# Forest-Joystick-Mouse-Hub.net
KiCad netlist of a schematic drawn in EAGLE
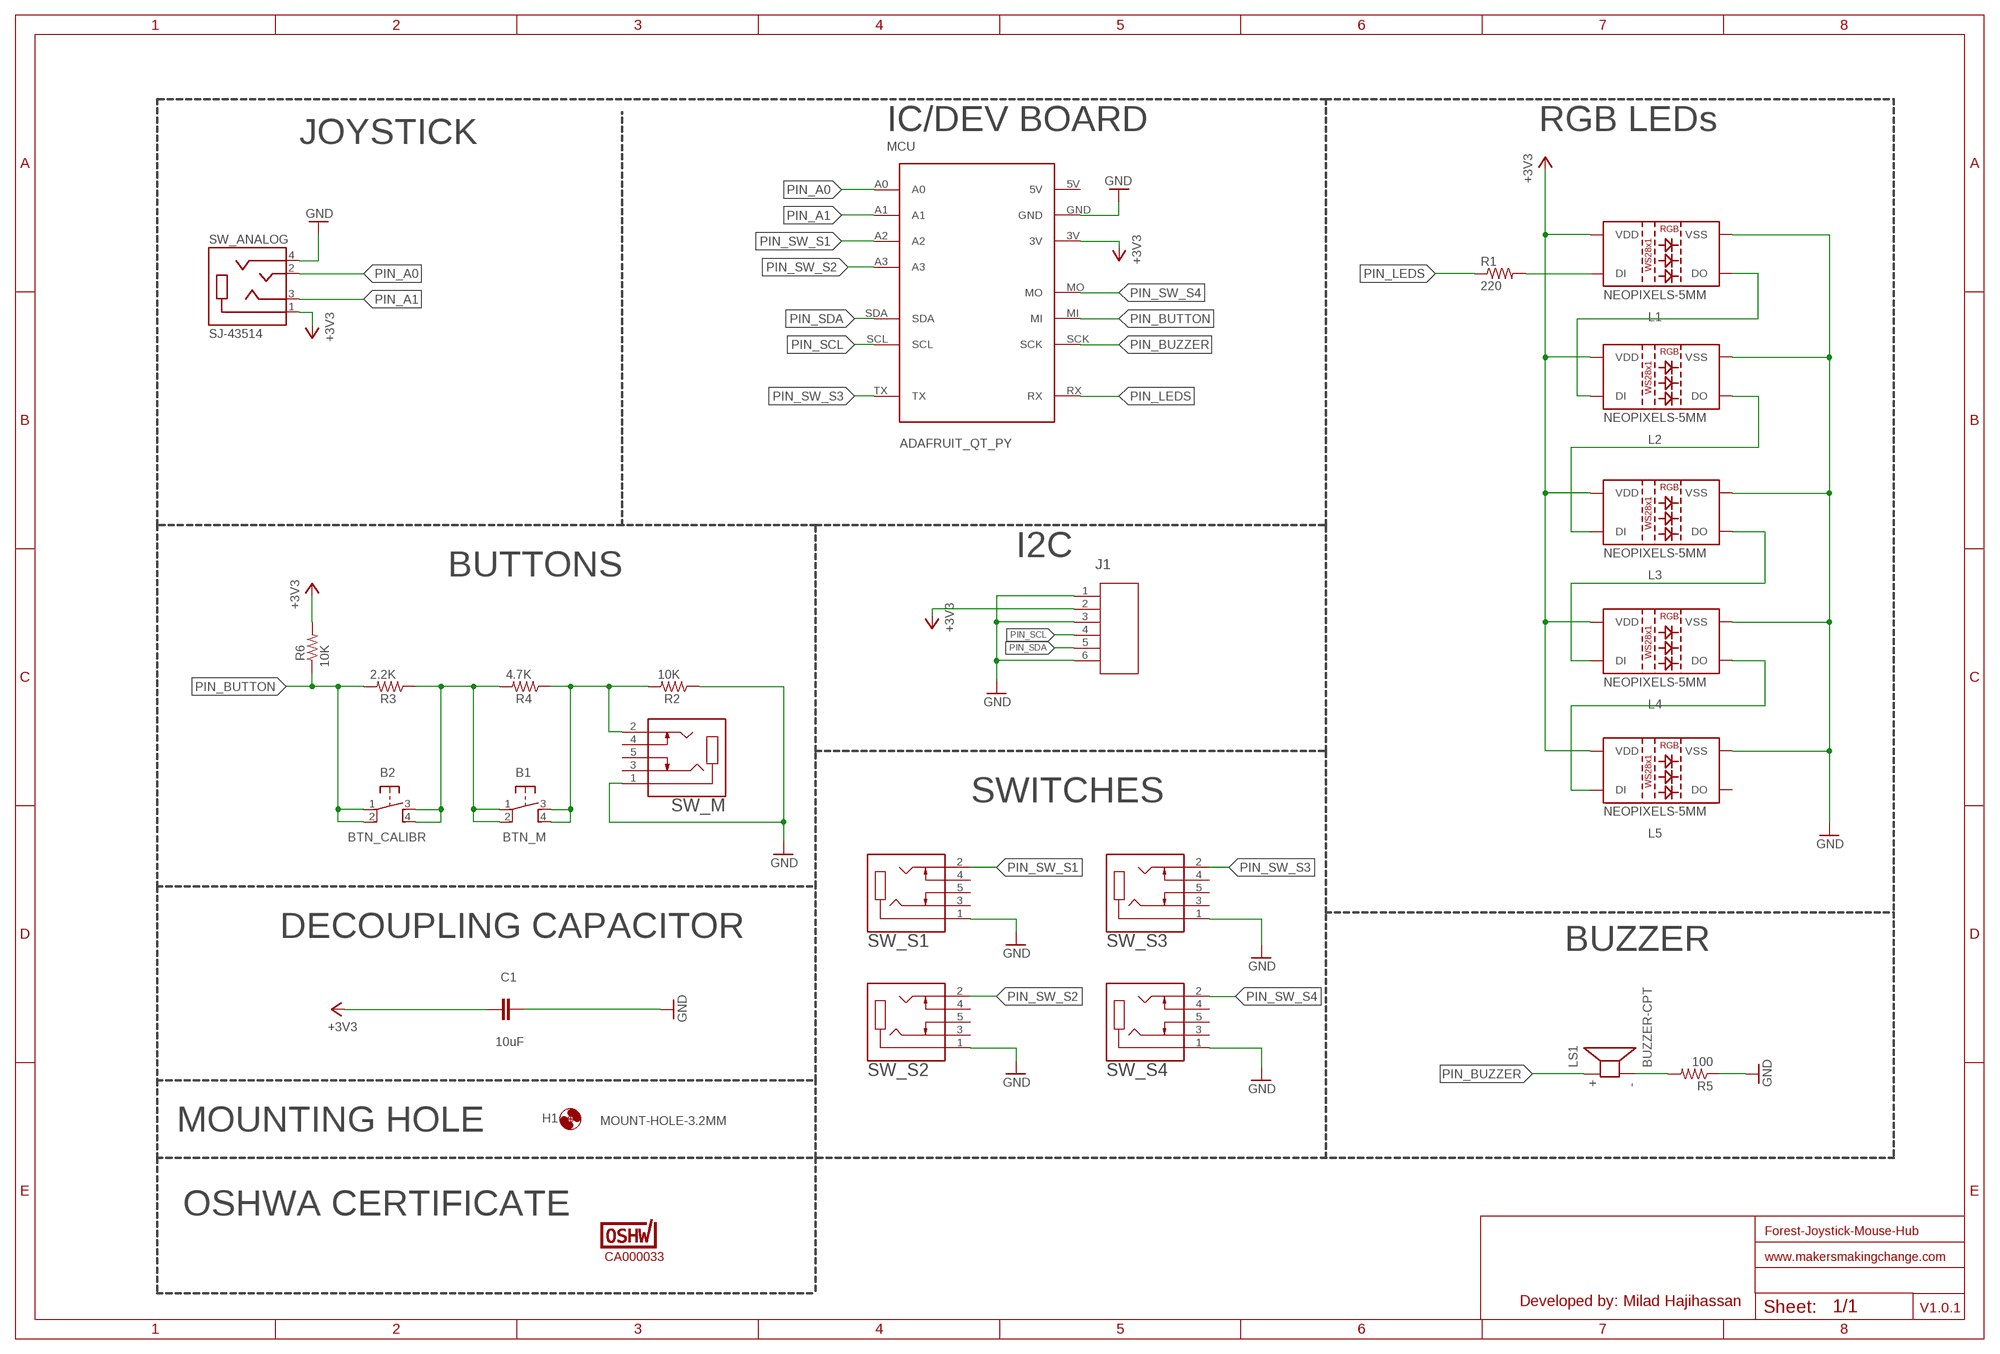
[diagram p0: schematic, sheet 1]

(export (version "E")
  (design (tool "Eeschema 10.0.6"))
  (components
    (comp (ref "B1")
      (value "BTN_M")
      (footprint "eagle-import:B3F-5050")
      (libsource (lib "eagle-import") (part "SWITCH_OMRON-PTH-12"))
    )
    (comp (ref "B2")
      (value "BTN_CALIBR")
      (footprint "eagle-import:B3F-5050")
      (libsource (lib "eagle-import") (part "SWITCH_OMRON-PTH-12"))
    )
    (comp (ref "C1")
      (value "10uF")
      (footprint "eagle-import:CAP-025-025X040")
      (libsource (lib "eagle-import") (part "CAPACITOR-025-025X040"))
    )
    (comp (ref "H1")
      (value "MOUNT-HOLE-3.2MM")
      (footprint "eagle-import:HOLE-3.2MM")
      (libsource (lib "eagle-import") (part "MOUNT-HOLE-3.2MM"))
    )
    (comp (ref "J1")
      (value "E5566-Q0LK22-L")
      (footprint "eagle-import:CONN6_E5566_PUL")
      (fields (field (name "COPYRIGHT") "Copyright (C) 2023 Ultra Librarian. All rights reserved."))
      (libsource (lib "eagle-import") (part "E5566-Q0LK22-L"))
    )
    (comp (ref "L1")
      (value "NEOPIXELS-5MM")
      (footprint "eagle-import:NEOPIXELS-5MM")
      (libsource (lib "eagle-import") (part "NEOPIXELS-5MM"))
    )
    (comp (ref "L2")
      (value "NEOPIXELS-5MM")
      (footprint "eagle-import:NEOPIXELS-5MM")
      (libsource (lib "eagle-import") (part "NEOPIXELS-5MM"))
    )
    (comp (ref "L3")
      (value "NEOPIXELS-5MM")
      (footprint "eagle-import:NEOPIXELS-5MM")
      (libsource (lib "eagle-import") (part "NEOPIXELS-5MM"))
    )
    (comp (ref "L4")
      (value "NEOPIXELS-5MM")
      (footprint "eagle-import:NEOPIXELS-5MM")
      (libsource (lib "eagle-import") (part "NEOPIXELS-5MM"))
    )
    (comp (ref "L5")
      (value "NEOPIXELS-5MM")
      (footprint "eagle-import:NEOPIXELS-5MM")
      (libsource (lib "eagle-import") (part "NEOPIXELS-5MM"))
    )
    (comp (ref "LOGO-OSHWA")
      (value "CA000033")
      (footprint "eagle-import:OSHWA-CERT-SMALL-SILK")
      (libsource (lib "eagle-import") (part "OSHWA-LOGO-SMALL"))
    )
    (comp (ref "LS1")
      (value "BUZZER-CPT")
      (footprint "eagle-import:CUI_CPT-1255C-090")
      (libsource (lib "eagle-import") (part "BUZZER-CPT"))
    )
    (comp (ref "MCU")
      (value "ADAFRUIT_QT_PY")
      (footprint "eagle-import:QT_PY")
      (libsource (lib "eagle-import") (part "ADAFRUIT_QT_PY"))
    )
    (comp (ref "R1")
      (value "220")
      (footprint "eagle-import:RESISTOR_0206_8")
      (libsource (lib "eagle-import") (part "RESISTOR-US-0206/8"))
    )
    (comp (ref "R2")
      (value "10K")
      (footprint "eagle-import:RESISTOR_0206_8")
      (libsource (lib "eagle-import") (part "RESISTOR-US-0206/8"))
    )
    (comp (ref "R3")
      (value "2.2K")
      (footprint "eagle-import:RESISTOR_0206_8")
      (libsource (lib "eagle-import") (part "RESISTOR-US-0206/8"))
    )
    (comp (ref "R4")
      (value "4.7K")
      (footprint "eagle-import:RESISTOR_0206_8")
      (libsource (lib "eagle-import") (part "RESISTOR-US-0206/8"))
    )
    (comp (ref "R5")
      (value "100")
      (footprint "eagle-import:RESISTOR_0206_8")
      (libsource (lib "eagle-import") (part "RESISTOR-US-0206/8"))
    )
    (comp (ref "R6")
      (value "10K")
      (footprint "eagle-import:RESISTOR_0206_8")
      (libsource (lib "eagle-import") (part "RESISTOR-US-0206/8"))
    )
    (comp (ref "SW_ANALOG")
      (value "SJ-43514")
      (footprint "eagle-import:CUI_SJ-43514")
      (libsource (lib "eagle-import") (part "SJ-43514"))
    )
    (comp (ref "SW_M")
      (value "CUI_SJ1-3535NGSJ1-3535NG")
      (footprint "eagle-import:CUI_SJ1-3535NG")
      (libsource (lib "eagle-import") (part "CUI_SJ1-3535NGSJ1-3535NG"))
    )
    (comp (ref "SW_S1")
      (value "CUI_SJ1-3535NGSJ1-3535NG")
      (footprint "eagle-import:CUI_SJ1-3535NG")
      (libsource (lib "eagle-import") (part "CUI_SJ1-3535NGSJ1-3535NG"))
    )
    (comp (ref "SW_S2")
      (value "CUI_SJ1-3535NGSJ1-3535NG")
      (footprint "eagle-import:CUI_SJ1-3535NG")
      (libsource (lib "eagle-import") (part "CUI_SJ1-3535NGSJ1-3535NG"))
    )
    (comp (ref "SW_S3")
      (value "CUI_SJ1-3535NGSJ1-3535NG")
      (footprint "eagle-import:CUI_SJ1-3535NG")
      (libsource (lib "eagle-import") (part "CUI_SJ1-3535NGSJ1-3535NG"))
    )
    (comp (ref "SW_S4")
      (value "CUI_SJ1-3535NGSJ1-3535NG")
      (footprint "eagle-import:CUI_SJ1-3535NG")
      (libsource (lib "eagle-import") (part "CUI_SJ1-3535NGSJ1-3535NG"))
    )
  )
  (nets
    (net (code "1") (name "+3V3") (class "Default")
      (node (ref "C1") (pin "1") (pinfunction "1_1") (pintype "passive"))
      (node (ref "J1") (pin "2") (pinfunction "2_2") (pintype "passive"))
      (node (ref "L1") (pin "P2") (pinfunction "VDD_P2") (pintype "bidirectional"))
      (node (ref "L2") (pin "P2") (pinfunction "VDD_P2") (pintype "bidirectional"))
      (node (ref "L3") (pin "P2") (pinfunction "VDD_P2") (pintype "bidirectional"))
      (node (ref "L4") (pin "P2") (pinfunction "VDD_P2") (pintype "bidirectional"))
      (node (ref "L5") (pin "P2") (pinfunction "VDD_P2") (pintype "bidirectional"))
      (node (ref "MCU") (pin "3V") (pinfunction "3V_3V") (pintype "bidirectional"))
      (node (ref "R6") (pin "2") (pinfunction "2_2") (pintype "passive"))
      (node (ref "SW_ANALOG") (pin "1") (pinfunction "SLEEVE_1") (pintype "passive"))
    )
    (net (code "2") (name "GND") (class "Default")
      (node (ref "C1") (pin "2") (pinfunction "2_2") (pintype "passive"))
      (node (ref "J1") (pin "1") (pinfunction "1_1") (pintype "passive"))
      (node (ref "J1") (pin "3") (pinfunction "3_3") (pintype "passive"))
      (node (ref "J1") (pin "6") (pinfunction "6_6") (pintype "passive"))
      (node (ref "L1") (pin "P3") (pinfunction "VSS_P3") (pintype "bidirectional"))
      (node (ref "L2") (pin "P3") (pinfunction "VSS_P3") (pintype "bidirectional"))
      (node (ref "L3") (pin "P3") (pinfunction "VSS_P3") (pintype "bidirectional"))
      (node (ref "L4") (pin "P3") (pinfunction "VSS_P3") (pintype "bidirectional"))
      (node (ref "L5") (pin "P3") (pinfunction "VSS_P3") (pintype "bidirectional"))
      (node (ref "MCU") (pin "GND") (pinfunction "GND_GND") (pintype "bidirectional"))
      (node (ref "R2") (pin "1") (pinfunction "1_1") (pintype "passive"))
      (node (ref "R5") (pin "1") (pinfunction "1_1") (pintype "passive"))
      (node (ref "SW_ANALOG") (pin "4") (pinfunction "RING2_4") (pintype "passive"))
      (node (ref "SW_M") (pin "1") (pinfunction "1_1") (pintype "passive"))
      (node (ref "SW_S1") (pin "1") (pinfunction "1_1") (pintype "passive"))
      (node (ref "SW_S2") (pin "1") (pinfunction "1_1") (pintype "passive"))
      (node (ref "SW_S3") (pin "1") (pinfunction "1_1") (pintype "passive"))
      (node (ref "SW_S4") (pin "1") (pinfunction "1_1") (pintype "passive"))
    )
    (net (code "3") (name "Net-(B1-Pad1)") (class "Default")
      (node (ref "B1") (pin "1") (pinfunction "1_1") (pintype "passive"))
      (node (ref "B1") (pin "2") (pinfunction "2_2") (pintype "passive"))
      (node (ref "B2") (pin "3") (pinfunction "3_3") (pintype "passive"))
      (node (ref "B2") (pin "4") (pinfunction "4_4") (pintype "passive"))
      (node (ref "R3") (pin "1") (pinfunction "1_1") (pintype "passive"))
      (node (ref "R4") (pin "2") (pinfunction "2_2") (pintype "passive"))
    )
    (net (code "4") (name "Net-(B1-Pad3)") (class "Default")
      (node (ref "B1") (pin "3") (pinfunction "3_3") (pintype "passive"))
      (node (ref "B1") (pin "4") (pinfunction "4_4") (pintype "passive"))
      (node (ref "R2") (pin "2") (pinfunction "2_2") (pintype "passive"))
      (node (ref "R4") (pin "1") (pinfunction "1_1") (pintype "passive"))
      (node (ref "SW_M") (pin "2") (pinfunction "2_2") (pintype "passive"))
    )
    (net (code "5") (name "Net-(L1-DI)") (class "Default")
      (node (ref "L1") (pin "P1") (pinfunction "DI_P1") (pintype "bidirectional"))
      (node (ref "R1") (pin "2") (pinfunction "2_2") (pintype "passive"))
    )
    (net (code "6") (name "Net-(L1-DO)") (class "Default")
      (node (ref "L1") (pin "P4") (pinfunction "DO_P4") (pintype "bidirectional"))
      (node (ref "L2") (pin "P1") (pinfunction "DI_P1") (pintype "bidirectional"))
    )
    (net (code "7") (name "Net-(L2-DO)") (class "Default")
      (node (ref "L2") (pin "P4") (pinfunction "DO_P4") (pintype "bidirectional"))
      (node (ref "L3") (pin "P1") (pinfunction "DI_P1") (pintype "bidirectional"))
    )
    (net (code "8") (name "Net-(L3-DO)") (class "Default")
      (node (ref "L3") (pin "P4") (pinfunction "DO_P4") (pintype "bidirectional"))
      (node (ref "L4") (pin "P1") (pinfunction "DI_P1") (pintype "bidirectional"))
    )
    (net (code "9") (name "Net-(L4-DO)") (class "Default")
      (node (ref "L4") (pin "P4") (pinfunction "DO_P4") (pintype "bidirectional"))
      (node (ref "L5") (pin "P1") (pinfunction "DI_P1") (pintype "bidirectional"))
    )
    (net (code "10") (name "Net-(LS1-PadN)") (class "Default")
      (node (ref "LS1") (pin "N") (pinfunction "N_N") (pintype "passive"))
      (node (ref "R5") (pin "2") (pinfunction "2_2") (pintype "passive"))
    )
    (net (code "11") (name "PIN_A0") (class "Default")
      (node (ref "MCU") (pin "A0") (pinfunction "A0_A0") (pintype "bidirectional"))
      (node (ref "SW_ANALOG") (pin "2") (pinfunction "TIP_2") (pintype "passive"))
    )
    (net (code "12") (name "PIN_A1") (class "Default")
      (node (ref "MCU") (pin "A1") (pinfunction "A1_A1") (pintype "bidirectional"))
      (node (ref "SW_ANALOG") (pin "3") (pinfunction "RING1_3") (pintype "passive"))
    )
    (net (code "13") (name "PIN_BUTTON") (class "Default")
      (node (ref "B2") (pin "1") (pinfunction "1_1") (pintype "passive"))
      (node (ref "B2") (pin "2") (pinfunction "2_2") (pintype "passive"))
      (node (ref "MCU") (pin "MI") (pinfunction "MI_MI") (pintype "bidirectional"))
      (node (ref "R3") (pin "2") (pinfunction "2_2") (pintype "passive"))
      (node (ref "R6") (pin "1") (pinfunction "1_1") (pintype "passive"))
    )
    (net (code "14") (name "PIN_BUZZER") (class "Default")
      (node (ref "LS1") (pin "P") (pinfunction "P_P") (pintype "passive"))
      (node (ref "MCU") (pin "SCK") (pinfunction "SCK_SCK") (pintype "bidirectional"))
    )
    (net (code "15") (name "PIN_LEDS") (class "Default")
      (node (ref "MCU") (pin "RX") (pinfunction "RX_RX") (pintype "bidirectional"))
      (node (ref "R1") (pin "1") (pinfunction "1_1") (pintype "passive"))
    )
    (net (code "16") (name "PIN_SCL") (class "Default")
      (node (ref "J1") (pin "4") (pinfunction "4_4") (pintype "passive"))
      (node (ref "MCU") (pin "SCL") (pinfunction "SCL_SCL") (pintype "bidirectional"))
    )
    (net (code "17") (name "PIN_SDA") (class "Default")
      (node (ref "J1") (pin "5") (pinfunction "5_5") (pintype "passive"))
      (node (ref "MCU") (pin "SDA") (pinfunction "SDA_SDA") (pintype "bidirectional"))
    )
    (net (code "18") (name "PIN_SW_S1") (class "Default")
      (node (ref "MCU") (pin "A2") (pinfunction "A2_A2") (pintype "bidirectional"))
      (node (ref "SW_S1") (pin "2") (pinfunction "2_2") (pintype "passive"))
    )
    (net (code "19") (name "PIN_SW_S2") (class "Default")
      (node (ref "MCU") (pin "A3") (pinfunction "A3_A3") (pintype "bidirectional"))
      (node (ref "SW_S2") (pin "2") (pinfunction "2_2") (pintype "passive"))
    )
    (net (code "20") (name "PIN_SW_S3") (class "Default")
      (node (ref "MCU") (pin "TX") (pinfunction "TX_TX") (pintype "bidirectional"))
      (node (ref "SW_S3") (pin "2") (pinfunction "2_2") (pintype "passive"))
    )
    (net (code "21") (name "PIN_SW_S4") (class "Default")
      (node (ref "MCU") (pin "MO") (pinfunction "MO_MO") (pintype "bidirectional"))
      (node (ref "SW_S4") (pin "2") (pinfunction "2_2") (pintype "passive"))
    )
    (net (code "22") (name "unconnected-(L5-DO-PadP4)") (class "Default")
      (node (ref "L5") (pin "P4") (pinfunction "DO_P4") (pintype "bidirectional"))
    )
    (net (code "23") (name "unconnected-(MCU-Pad5V)") (class "Default")
      (node (ref "MCU") (pin "5V") (pinfunction "5V_5V") (pintype "bidirectional"))
    )
    (net (code "24") (name "unconnected-(SW_M-Pad3)") (class "Default")
      (node (ref "SW_M") (pin "3") (pinfunction "3_3") (pintype "passive"))
    )
    (net (code "25") (name "unconnected-(SW_M-Pad4)") (class "Default")
      (node (ref "SW_M") (pin "4") (pinfunction "4_4") (pintype "passive"))
    )
    (net (code "26") (name "unconnected-(SW_M-Pad5)") (class "Default")
      (node (ref "SW_M") (pin "5") (pinfunction "5_5") (pintype "passive"))
    )
    (net (code "27") (name "unconnected-(SW_S1-Pad3)") (class "Default")
      (node (ref "SW_S1") (pin "3") (pinfunction "3_3") (pintype "passive"))
    )
    (net (code "28") (name "unconnected-(SW_S1-Pad4)") (class "Default")
      (node (ref "SW_S1") (pin "4") (pinfunction "4_4") (pintype "passive"))
    )
    (net (code "29") (name "unconnected-(SW_S1-Pad5)") (class "Default")
      (node (ref "SW_S1") (pin "5") (pinfunction "5_5") (pintype "passive"))
    )
    (net (code "30") (name "unconnected-(SW_S2-Pad3)") (class "Default")
      (node (ref "SW_S2") (pin "3") (pinfunction "3_3") (pintype "passive"))
    )
    (net (code "31") (name "unconnected-(SW_S2-Pad4)") (class "Default")
      (node (ref "SW_S2") (pin "4") (pinfunction "4_4") (pintype "passive"))
    )
    (net (code "32") (name "unconnected-(SW_S2-Pad5)") (class "Default")
      (node (ref "SW_S2") (pin "5") (pinfunction "5_5") (pintype "passive"))
    )
    (net (code "33") (name "unconnected-(SW_S3-Pad3)") (class "Default")
      (node (ref "SW_S3") (pin "3") (pinfunction "3_3") (pintype "passive"))
    )
    (net (code "34") (name "unconnected-(SW_S3-Pad4)") (class "Default")
      (node (ref "SW_S3") (pin "4") (pinfunction "4_4") (pintype "passive"))
    )
    (net (code "35") (name "unconnected-(SW_S3-Pad5)") (class "Default")
      (node (ref "SW_S3") (pin "5") (pinfunction "5_5") (pintype "passive"))
    )
    (net (code "36") (name "unconnected-(SW_S4-Pad3)") (class "Default")
      (node (ref "SW_S4") (pin "3") (pinfunction "3_3") (pintype "passive"))
    )
    (net (code "37") (name "unconnected-(SW_S4-Pad4)") (class "Default")
      (node (ref "SW_S4") (pin "4") (pinfunction "4_4") (pintype "passive"))
    )
    (net (code "38") (name "unconnected-(SW_S4-Pad5)") (class "Default")
      (node (ref "SW_S4") (pin "5") (pinfunction "5_5") (pintype "passive"))
    )
  )
)
